# E1706R_Schematic_1.net
KiCad netlist of a schematic drawn in Altium Designer
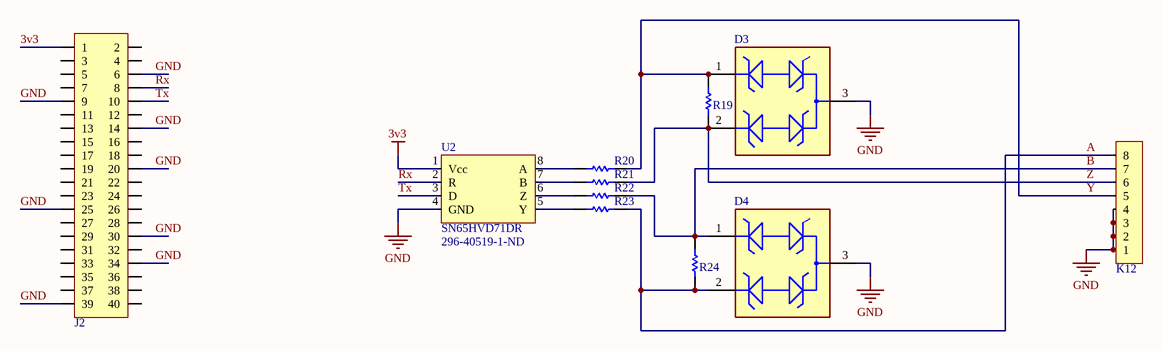
[diagram p0: E1706R_Schematic_1.SchDoc]

(export (version "E")
  (design (tool "Eeschema 10.0.6"))
  (components
    (comp (ref "D3")
      (value "CDSOT23-SM712")
      (footprint "FP-SOT23-MFG")
      (description "TVS DIODE 7V/12V 14V/26V SOT23-3")
      (fields
        (field (name "MANUFACTURER") "Bourns Inc.")
        (field (name "OCTOPART") "https://octopart.com/cdsot23-sm712-bourns-7576327")
      )
      (libsource (lib "Altium Content Vault") (part "81303f94231262926866863442dad16"))
    )
    (comp (ref "D4")
      (value "CDSOT23-SM712")
      (footprint "FP-SOT23-MFG")
      (description "TVS DIODE 7V/12V 14V/26V SOT23-3")
      (fields
        (field (name "MANUFACTURER") "Bourns Inc.")
        (field (name "OCTOPART") "https://octopart.com/cdsot23-sm712-bourns-7576327")
      )
      (libsource (lib "Altium Content Vault") (part "81303f94231262926866863442dad16"))
    )
    (comp (ref "J2")
      (value "2223")
      (footprint "2223")
      (description "40 PIN 20X2 CONN")
      (libsource (lib "SchLibrary") (part "2223"))
    )
    (comp (ref "K12")
      (value "6339191-5")
      (footprint "6339191-5")
      (libsource (lib "SchLibrary") (part "6339191-5"))
    )
    (comp (ref "R19")
      (value "Res_120_0805")
      (footprint "RESC2012N")
      (description "RES 120 OHM 1/8W 1% 0805")
      (libsource (lib "Erico_Ignitor") (part "Res_120_0805"))
    )
    (comp (ref "R20")
      (value "Res_10_0805")
      (footprint "RESC2012N")
      (description "RES 10 OHM 1/8W 1% 0805")
      (fields (field (name "MANUFACTURER") "Vishay Dale") (field (name "TOLERANCE") "±1%"))
      (libsource (lib "Erico_Ignitor") (part "Res_10_0805"))
    )
    (comp (ref "R21")
      (value "Res_10_0805")
      (footprint "RESC2012N")
      (description "RES 10 OHM 1/8W 1% 0805")
      (fields (field (name "MANUFACTURER") "Vishay Dale") (field (name "TOLERANCE") "±1%"))
      (libsource (lib "Erico_Ignitor") (part "Res_10_0805"))
    )
    (comp (ref "R22")
      (value "Res_10_0805")
      (footprint "RESC2012N")
      (description "RES 10 OHM 1/8W 1% 0805")
      (fields (field (name "MANUFACTURER") "Vishay Dale") (field (name "TOLERANCE") "±1%"))
      (libsource (lib "Erico_Ignitor") (part "Res_10_0805"))
    )
    (comp (ref "R23")
      (value "Res_10_0805")
      (footprint "RESC2012N")
      (description "RES 10 OHM 1/8W 1% 0805")
      (fields (field (name "MANUFACTURER") "Vishay Dale") (field (name "TOLERANCE") "±1%"))
      (libsource (lib "Erico_Ignitor") (part "Res_10_0805"))
    )
    (comp (ref "R24")
      (value "Res_120_0805")
      (footprint "RESC2012N")
      (description "RES 120 OHM 1/8W 1% 0805")
      (libsource (lib "Erico_Ignitor") (part "Res_120_0805"))
    )
    (comp (ref "U2")
      (value "SN65HVD71DR")
      (footprint "SN65HVD71DR")
      (description "Single Transmitter/Receiver RS-485 8-Pin SOIC T/R")
      (fields
        (field (name "SUPPLIER PART NUMBER 1") "296-40519-1-ND")
        (field (name "MANUFACTURER") "Texas Instruments")
      )
      (libsource (lib "SchLibrary") (part "SN65HVD71DR"))
    )
  )
  (nets
    (net (code "1") (name "/A") (class "Default")
      (node (ref "D4") (pin "2") (pinfunction "2_2") (pintype "passive"))
      (node (ref "K12") (pin "8") (pinfunction "8_8") (pintype "passive"))
      (node (ref "R23") (pin "2") (pinfunction "2_2") (pintype "passive"))
      (node (ref "R24") (pin "1") (pinfunction "1_1") (pintype "passive"))
    )
    (net (code "2") (name "/B") (class "Default")
      (node (ref "D4") (pin "1") (pinfunction "1_1") (pintype "passive"))
      (node (ref "K12") (pin "7") (pinfunction "7_7") (pintype "passive"))
      (node (ref "R22") (pin "2") (pinfunction "2_2") (pintype "passive"))
      (node (ref "R24") (pin "2") (pinfunction "2_2") (pintype "passive"))
    )
    (net (code "3") (name "/Rx") (class "Default")
      (node (ref "J2") (pin "8") (pinfunction "8_8") (pintype "passive"))
      (node (ref "U2") (pin "2") (pinfunction "R_2") (pintype "passive"))
    )
    (net (code "4") (name "/Tx") (class "Default")
      (node (ref "J2") (pin "10") (pinfunction "10_10") (pintype "passive"))
      (node (ref "U2") (pin "3") (pinfunction "D_3") (pintype "passive"))
    )
    (net (code "5") (name "/Y") (class "Default")
      (node (ref "D3") (pin "1") (pinfunction "1_1") (pintype "passive"))
      (node (ref "K12") (pin "5") (pinfunction "5_5") (pintype "passive"))
      (node (ref "R19") (pin "2") (pinfunction "2_2") (pintype "passive"))
      (node (ref "R20") (pin "2") (pinfunction "2_2") (pintype "passive"))
    )
    (net (code "6") (name "/Z") (class "Default")
      (node (ref "D3") (pin "2") (pinfunction "2_2") (pintype "passive"))
      (node (ref "K12") (pin "6") (pinfunction "6_6") (pintype "passive"))
      (node (ref "R19") (pin "1") (pinfunction "1_1") (pintype "passive"))
      (node (ref "R21") (pin "2") (pinfunction "2_2") (pintype "passive"))
    )
    (net (code "7") (name "3v3") (class "Default")
      (node (ref "J2") (pin "1") (pinfunction "1_1") (pintype "passive"))
      (node (ref "U2") (pin "1") (pinfunction "Vcc_1") (pintype "passive"))
    )
    (net (code "8") (name "GND") (class "Default")
      (node (ref "D3") (pin "3") (pinfunction "3_3") (pintype "passive"))
      (node (ref "D4") (pin "3") (pinfunction "3_3") (pintype "passive"))
      (node (ref "J2") (pin "14") (pinfunction "14_14") (pintype "passive"))
      (node (ref "J2") (pin "20") (pinfunction "20_20") (pintype "passive"))
      (node (ref "J2") (pin "25") (pinfunction "25_25") (pintype "passive"))
      (node (ref "J2") (pin "30") (pinfunction "30_30") (pintype "passive"))
      (node (ref "J2") (pin "34") (pinfunction "34_34") (pintype "passive"))
      (node (ref "J2") (pin "39") (pinfunction "39_39") (pintype "passive"))
      (node (ref "J2") (pin "6") (pinfunction "6_6") (pintype "passive"))
      (node (ref "J2") (pin "9") (pinfunction "9_9") (pintype "passive"))
      (node (ref "K12") (pin "1") (pinfunction "1_1") (pintype "passive"))
      (node (ref "K12") (pin "2") (pinfunction "2_2") (pintype "passive"))
      (node (ref "K12") (pin "3") (pinfunction "3_3") (pintype "passive"))
      (node (ref "K12") (pin "4") (pinfunction "4_4") (pintype "passive"))
      (node (ref "U2") (pin "4") (pinfunction "GND_4") (pintype "passive"))
    )
    (net (code "9") (name "Net-(U2-A)") (class "Default")
      (node (ref "R20") (pin "1") (pinfunction "1_1") (pintype "passive"))
      (node (ref "U2") (pin "8") (pinfunction "A_8") (pintype "passive"))
    )
    (net (code "10") (name "Net-(U2-B)") (class "Default")
      (node (ref "R21") (pin "1") (pinfunction "1_1") (pintype "passive"))
      (node (ref "U2") (pin "7") (pinfunction "B_7") (pintype "passive"))
    )
    (net (code "11") (name "Net-(U2-Y)") (class "Default")
      (node (ref "R23") (pin "1") (pinfunction "1_1") (pintype "passive"))
      (node (ref "U2") (pin "5") (pinfunction "Y_5") (pintype "passive"))
    )
    (net (code "12") (name "Net-(U2-Z)") (class "Default")
      (node (ref "R22") (pin "1") (pinfunction "1_1") (pintype "passive"))
      (node (ref "U2") (pin "6") (pinfunction "Z_6") (pintype "passive"))
    )
    (net (code "13") (name "unconnected-(J2-Pad2)") (class "Default")
      (node (ref "J2") (pin "2") (pinfunction "2_2") (pintype "passive"))
    )
    (net (code "14") (name "unconnected-(J2-Pad3)") (class "Default")
      (node (ref "J2") (pin "3") (pinfunction "3_3") (pintype "passive"))
    )
    (net (code "15") (name "unconnected-(J2-Pad4)") (class "Default")
      (node (ref "J2") (pin "4") (pinfunction "4_4") (pintype "passive"))
    )
    (net (code "16") (name "unconnected-(J2-Pad5)") (class "Default")
      (node (ref "J2") (pin "5") (pinfunction "5_5") (pintype "passive"))
    )
    (net (code "17") (name "unconnected-(J2-Pad7)") (class "Default")
      (node (ref "J2") (pin "7") (pinfunction "7_7") (pintype "passive"))
    )
    (net (code "18") (name "unconnected-(J2-Pad11)") (class "Default")
      (node (ref "J2") (pin "11") (pinfunction "11_11") (pintype "passive"))
    )
    (net (code "19") (name "unconnected-(J2-Pad12)") (class "Default")
      (node (ref "J2") (pin "12") (pinfunction "12_12") (pintype "passive"))
    )
    (net (code "20") (name "unconnected-(J2-Pad13)") (class "Default")
      (node (ref "J2") (pin "13") (pinfunction "13_13") (pintype "passive"))
    )
    (net (code "21") (name "unconnected-(J2-Pad15)") (class "Default")
      (node (ref "J2") (pin "15") (pinfunction "15_15") (pintype "passive"))
    )
    (net (code "22") (name "unconnected-(J2-Pad16)") (class "Default")
      (node (ref "J2") (pin "16") (pinfunction "16_16") (pintype "passive"))
    )
    (net (code "23") (name "unconnected-(J2-Pad17)") (class "Default")
      (node (ref "J2") (pin "17") (pinfunction "17_17") (pintype "passive"))
    )
    (net (code "24") (name "unconnected-(J2-Pad18)") (class "Default")
      (node (ref "J2") (pin "18") (pinfunction "18_18") (pintype "passive"))
    )
    (net (code "25") (name "unconnected-(J2-Pad19)") (class "Default")
      (node (ref "J2") (pin "19") (pinfunction "19_19") (pintype "passive"))
    )
    (net (code "26") (name "unconnected-(J2-Pad21)") (class "Default")
      (node (ref "J2") (pin "21") (pinfunction "21_21") (pintype "passive"))
    )
    (net (code "27") (name "unconnected-(J2-Pad22)") (class "Default")
      (node (ref "J2") (pin "22") (pinfunction "22_22") (pintype "passive"))
    )
    (net (code "28") (name "unconnected-(J2-Pad23)") (class "Default")
      (node (ref "J2") (pin "23") (pinfunction "23_23") (pintype "passive"))
    )
    (net (code "29") (name "unconnected-(J2-Pad24)") (class "Default")
      (node (ref "J2") (pin "24") (pinfunction "24_24") (pintype "passive"))
    )
    (net (code "30") (name "unconnected-(J2-Pad26)") (class "Default")
      (node (ref "J2") (pin "26") (pinfunction "26_26") (pintype "passive"))
    )
    (net (code "31") (name "unconnected-(J2-Pad27)") (class "Default")
      (node (ref "J2") (pin "27") (pinfunction "27_27") (pintype "passive"))
    )
    (net (code "32") (name "unconnected-(J2-Pad28)") (class "Default")
      (node (ref "J2") (pin "28") (pinfunction "28_28") (pintype "passive"))
    )
    (net (code "33") (name "unconnected-(J2-Pad29)") (class "Default")
      (node (ref "J2") (pin "29") (pinfunction "29_29") (pintype "passive"))
    )
    (net (code "34") (name "unconnected-(J2-Pad31)") (class "Default")
      (node (ref "J2") (pin "31") (pinfunction "31_31") (pintype "passive"))
    )
    (net (code "35") (name "unconnected-(J2-Pad32)") (class "Default")
      (node (ref "J2") (pin "32") (pinfunction "32_32") (pintype "passive"))
    )
    (net (code "36") (name "unconnected-(J2-Pad33)") (class "Default")
      (node (ref "J2") (pin "33") (pinfunction "33_33") (pintype "passive"))
    )
    (net (code "37") (name "unconnected-(J2-Pad35)") (class "Default")
      (node (ref "J2") (pin "35") (pinfunction "35_35") (pintype "passive"))
    )
    (net (code "38") (name "unconnected-(J2-Pad36)") (class "Default")
      (node (ref "J2") (pin "36") (pinfunction "36_36") (pintype "passive"))
    )
    (net (code "39") (name "unconnected-(J2-Pad37)") (class "Default")
      (node (ref "J2") (pin "37") (pinfunction "37_37") (pintype "passive"))
    )
    (net (code "40") (name "unconnected-(J2-Pad38)") (class "Default")
      (node (ref "J2") (pin "38") (pinfunction "38_38") (pintype "passive"))
    )
    (net (code "41") (name "unconnected-(J2-Pad40)") (class "Default")
      (node (ref "J2") (pin "40") (pinfunction "40_40") (pintype "passive"))
    )
  )
)
